# untitled.net
KiCad netlist of a schematic drawn in EAGLE
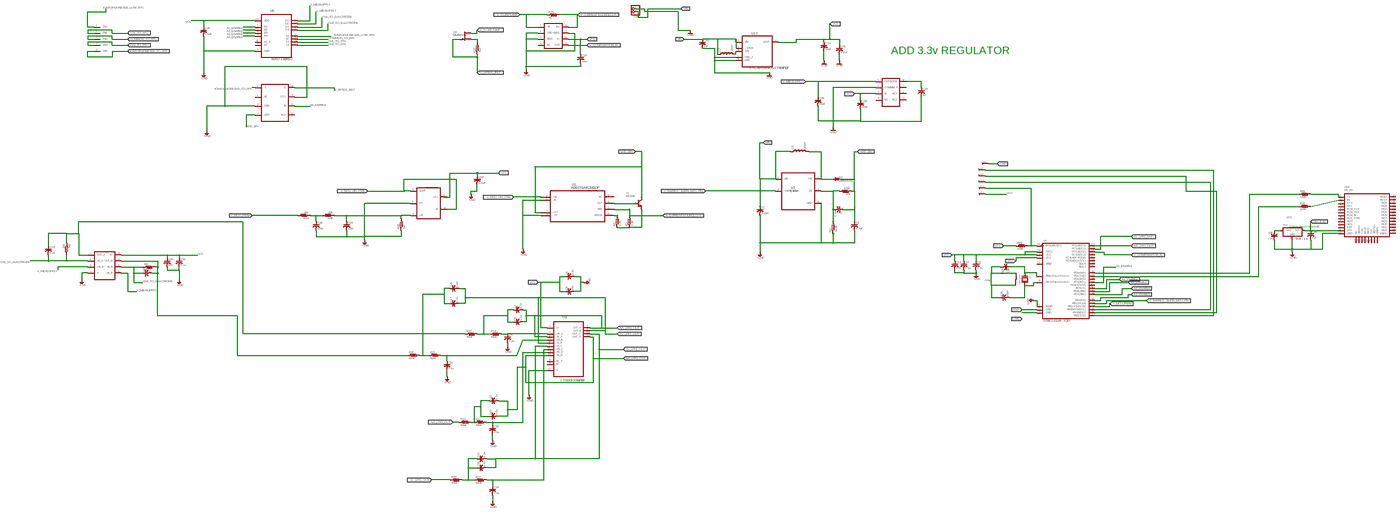
[diagram p0: schematic, sheet 1, overview]
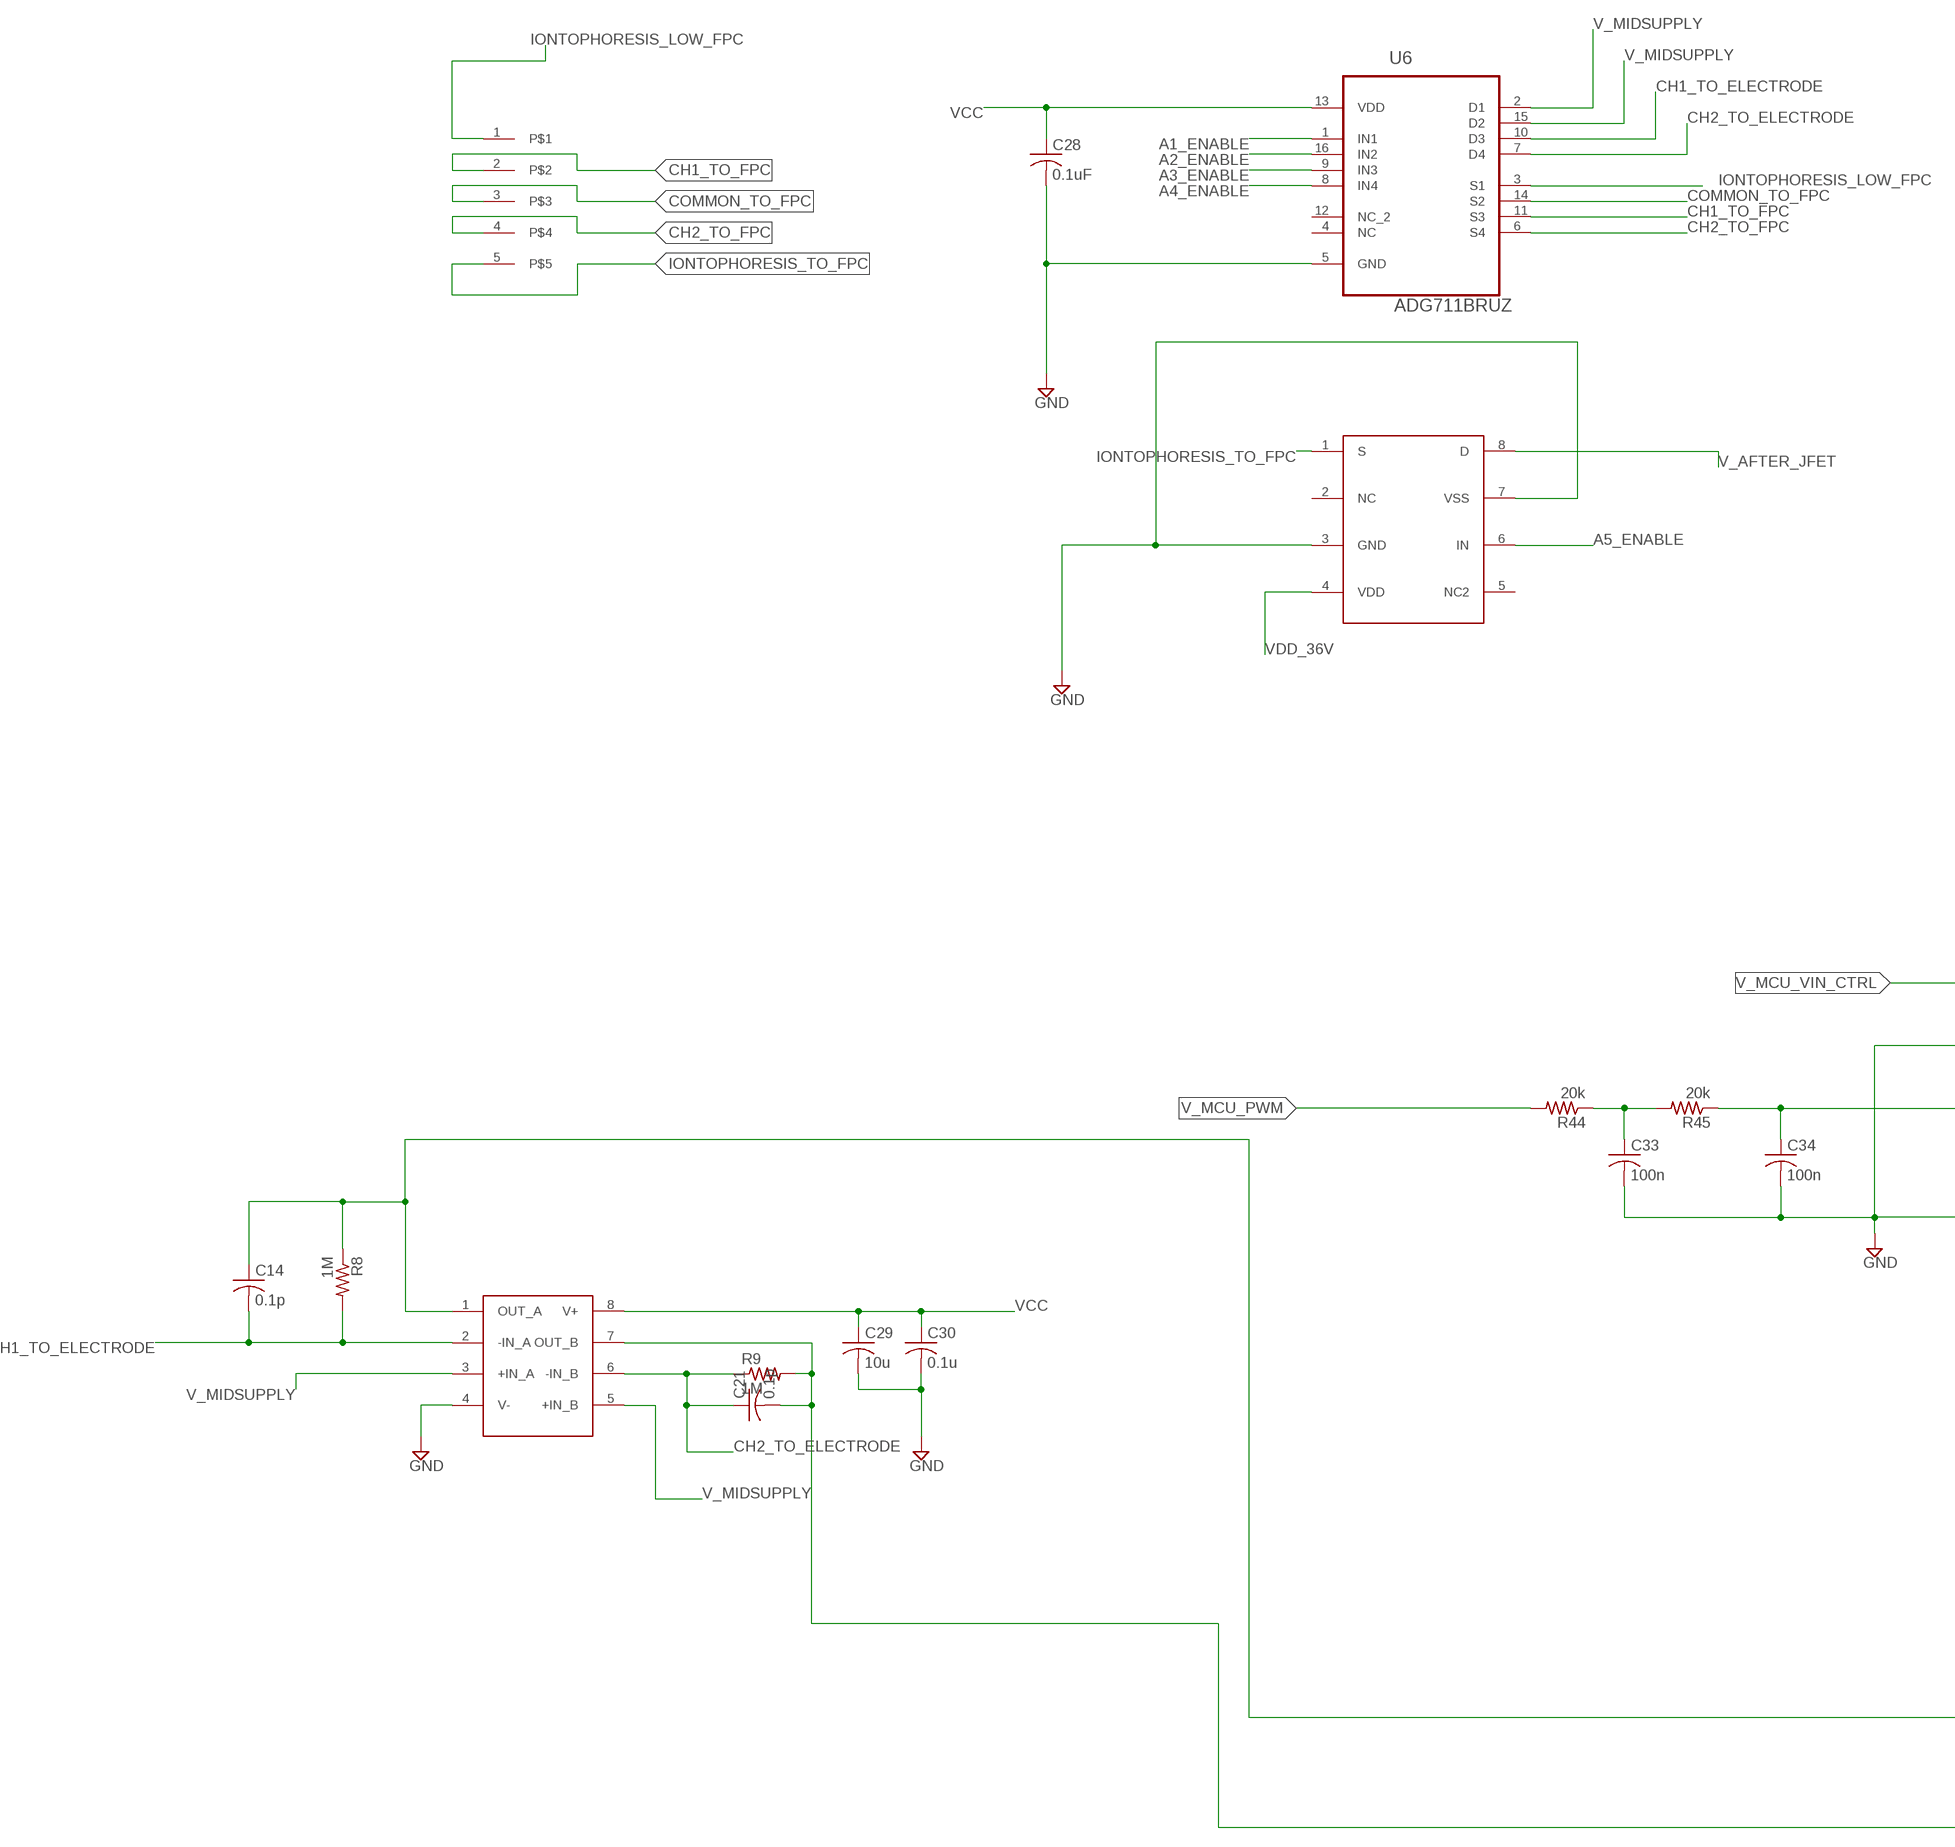
[diagram p1: schematic, sheet 1, part 1 of 4]
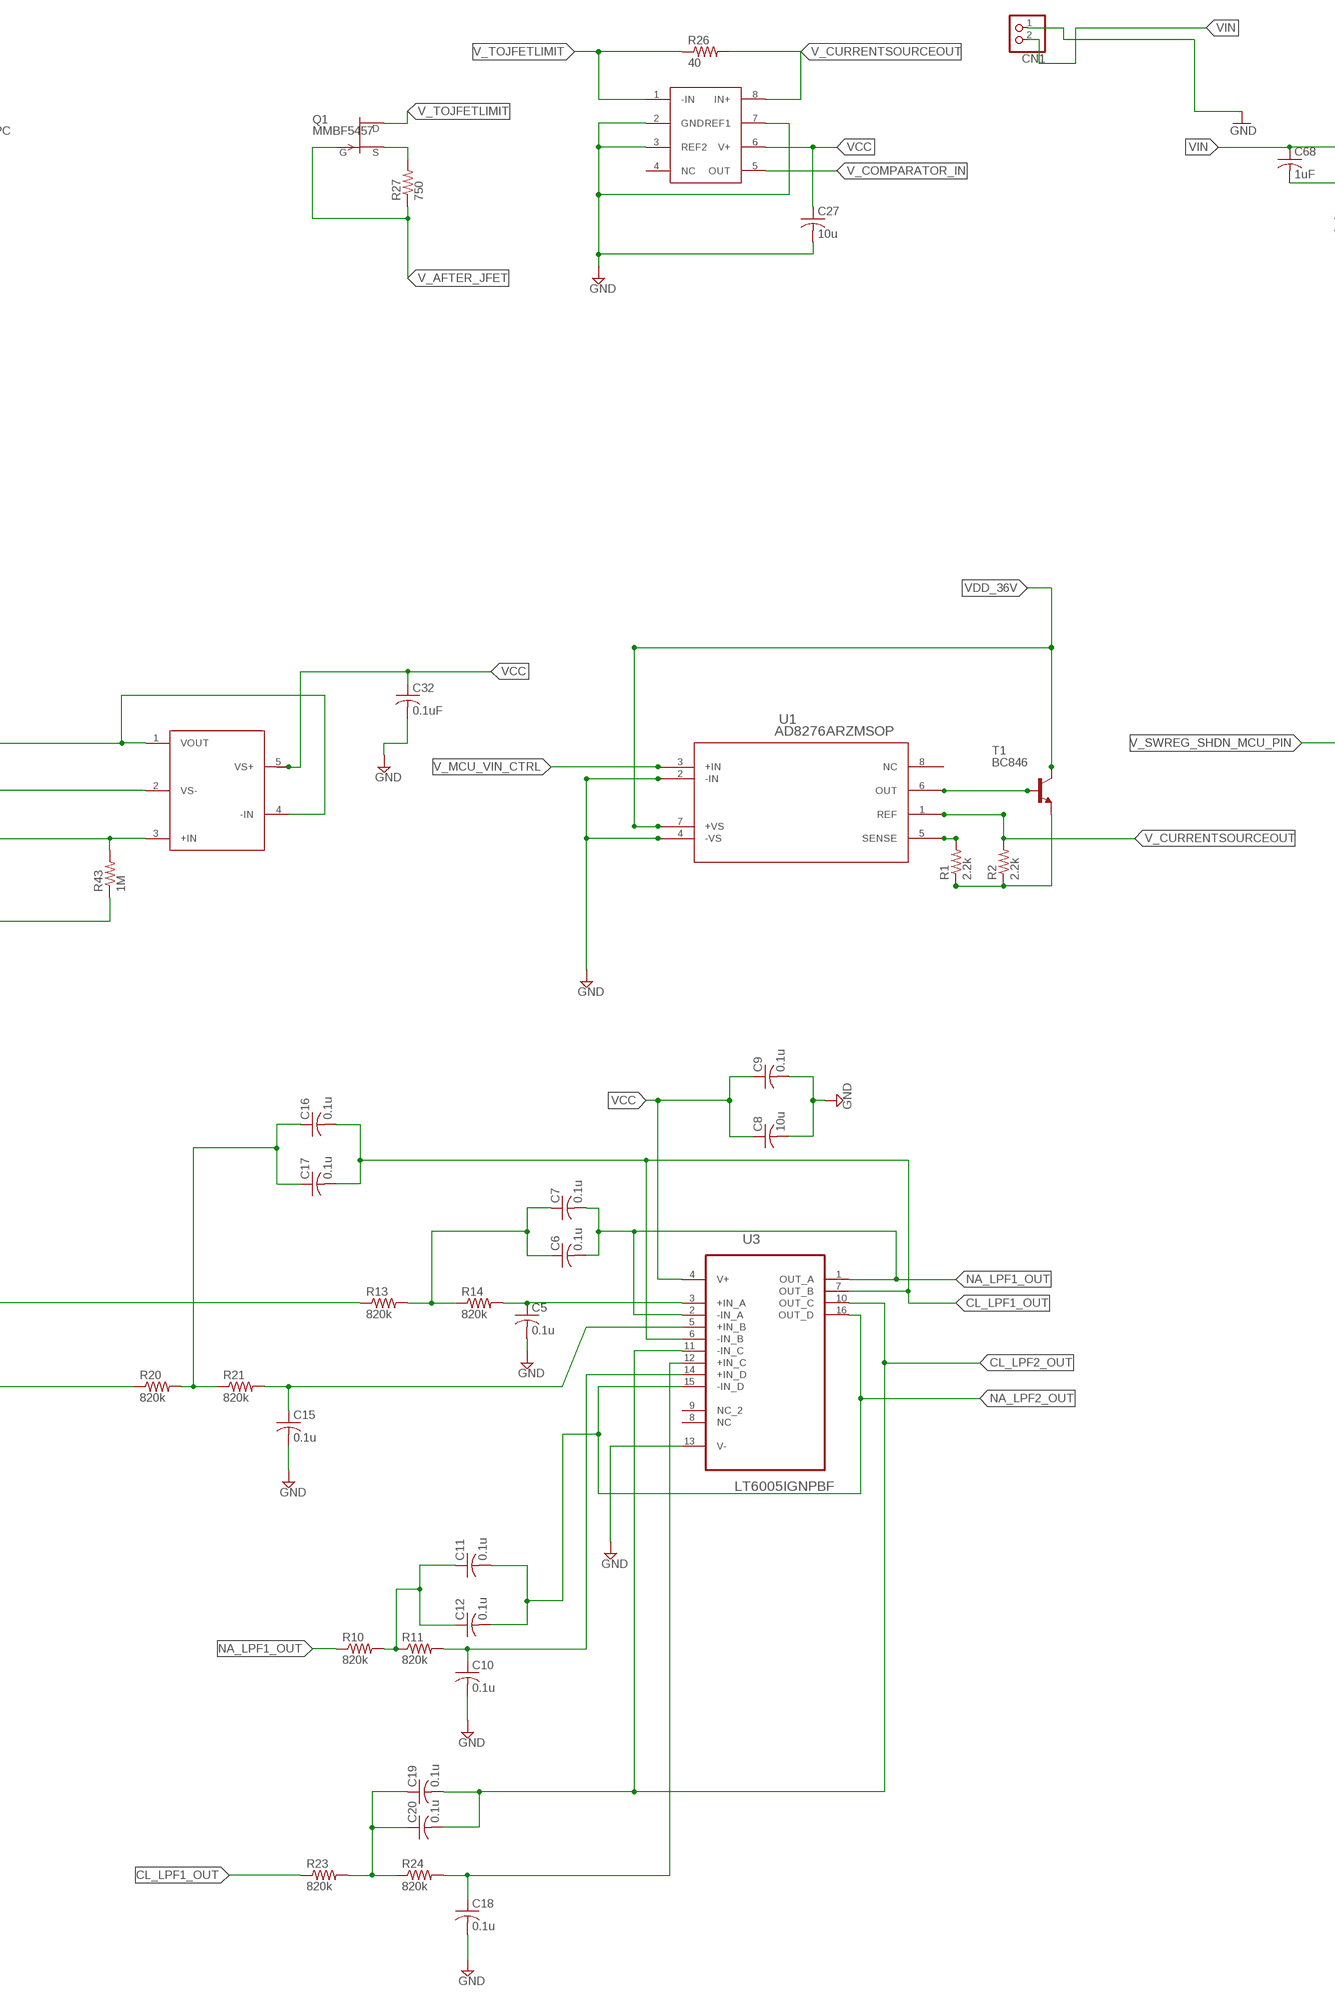
[diagram p2: schematic, sheet 1, part 2 of 4]
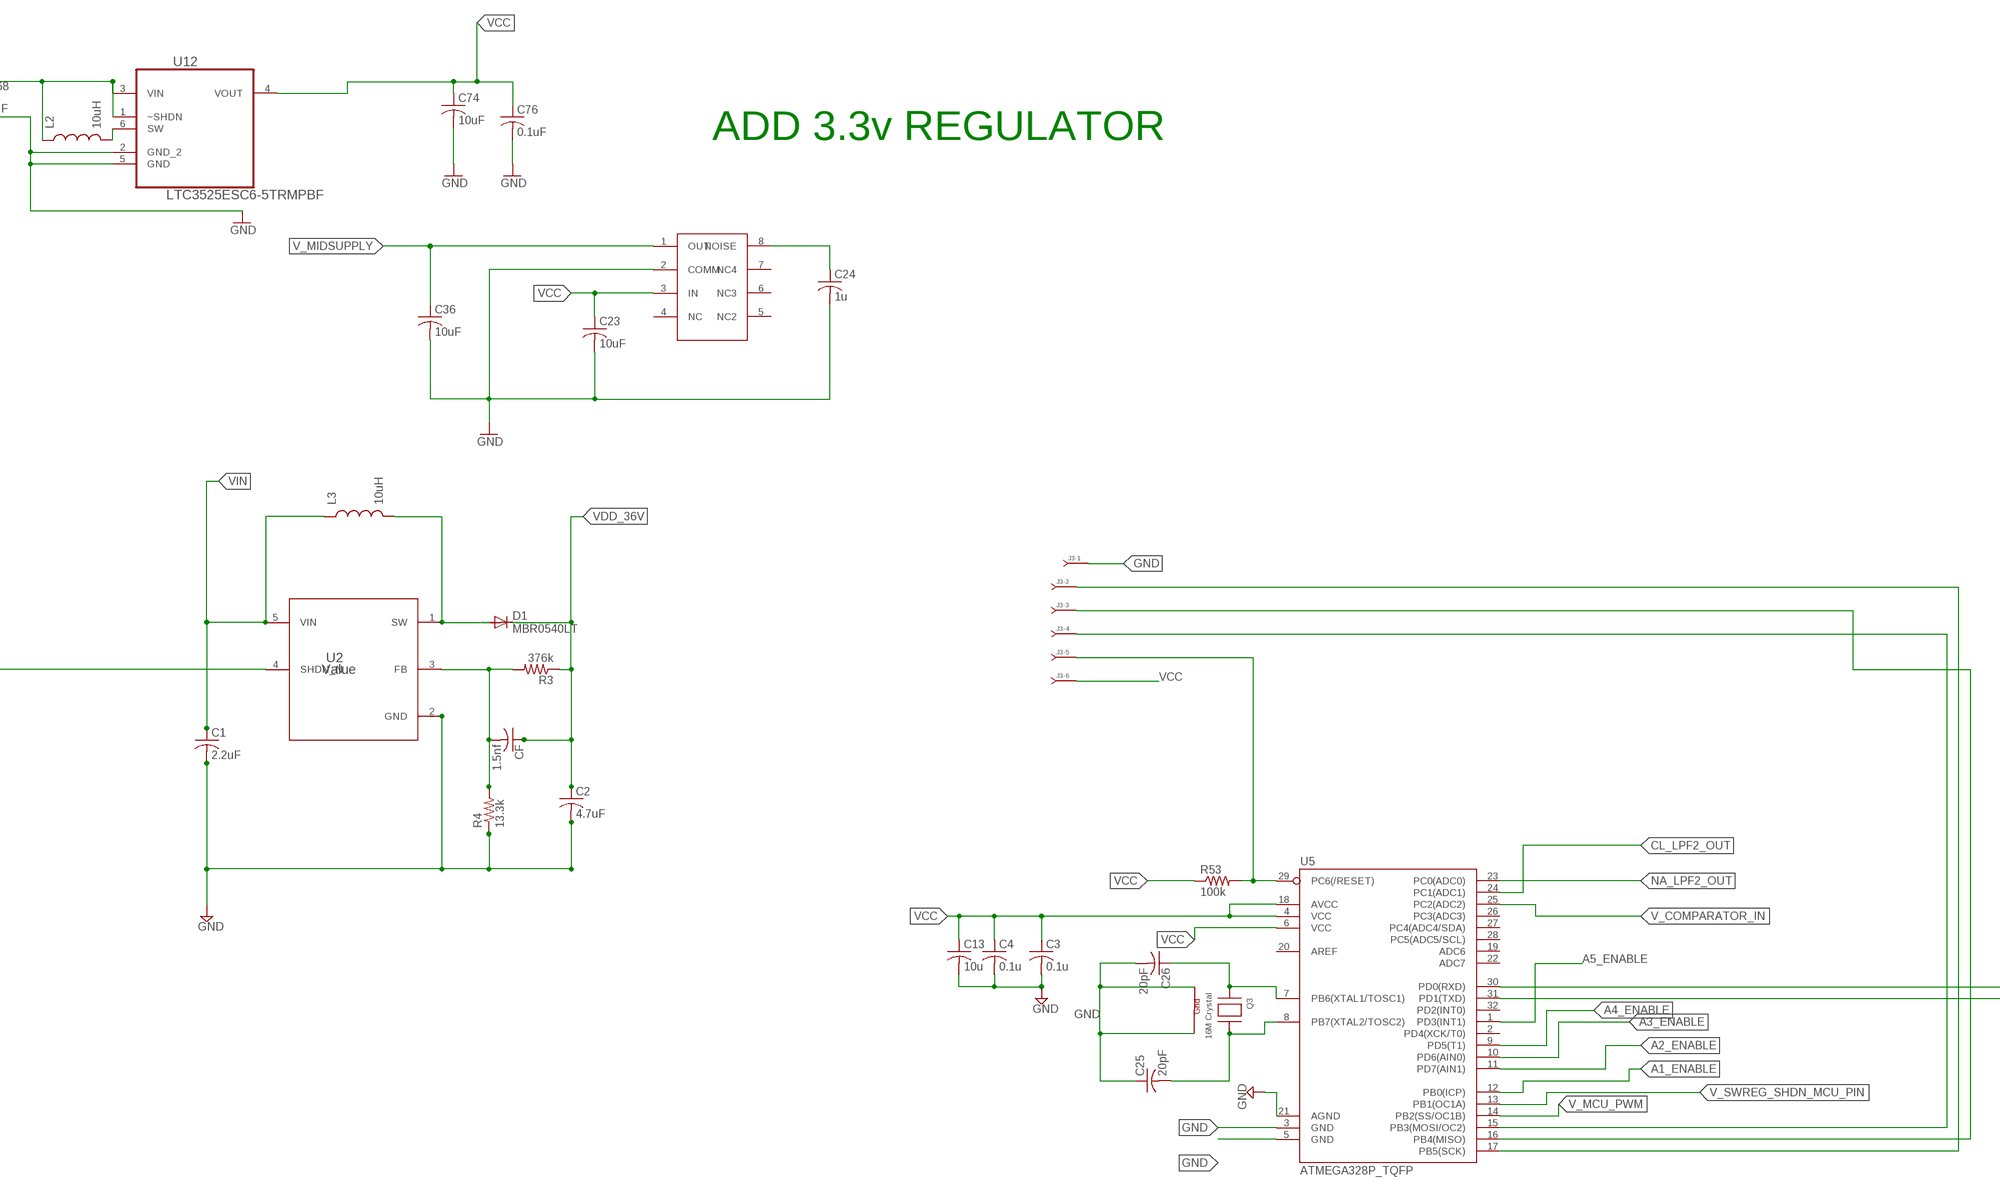
[diagram p3: schematic, sheet 1, part 3 of 4]
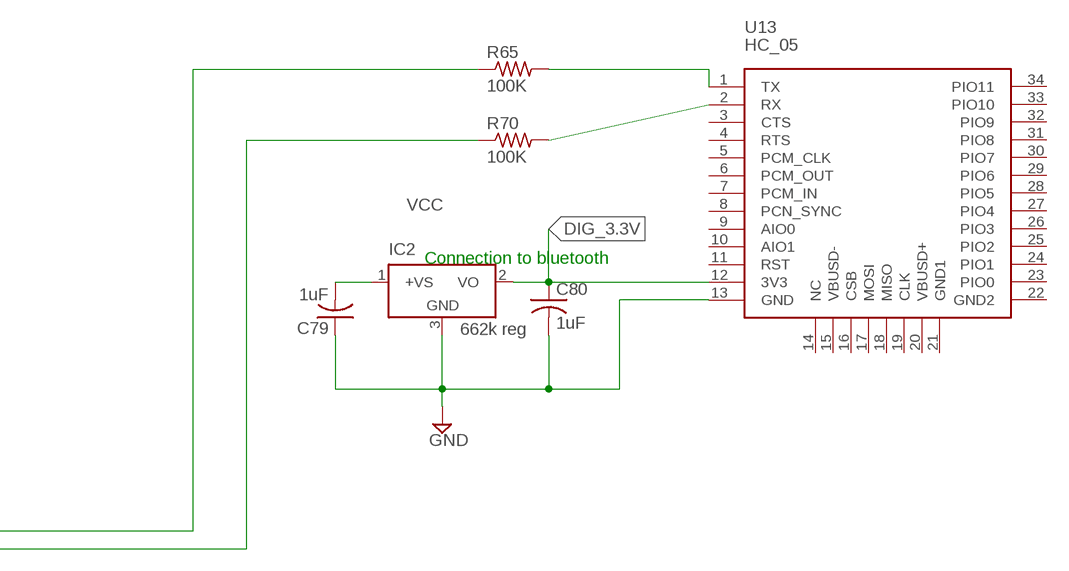
[diagram p4: schematic, sheet 1, part 4 of 4]

(export (version "E")
  (design (tool "Eeschema 10.0.6"))
  (components
    (comp (ref "C1")
      (value "2.2uF")
      (footprint "eagle-import:C0402")
      (libsource (lib "eagle-import") (part "resistor_C-USC0402"))
    )
    (comp (ref "C2")
      (value "4.7uF")
      (footprint "eagle-import:C0603")
      (libsource (lib "eagle-import") (part "resistor_C-USC0603"))
    )
    (comp (ref "C3")
      (value "0.1u")
      (footprint "eagle-import:C0201")
      (libsource (lib "eagle-import") (part "C-USC0201"))
    )
    (comp (ref "C4")
      (value "0.1u")
      (footprint "eagle-import:C0201")
      (libsource (lib "eagle-import") (part "C-USC0201"))
    )
    (comp (ref "C5")
      (value "0.1u")
      (footprint "eagle-import:C0201")
      (libsource (lib "eagle-import") (part "C-USC0201"))
    )
    (comp (ref "C6")
      (value "0.1u")
      (footprint "eagle-import:C0201")
      (libsource (lib "eagle-import") (part "C-USC0201"))
    )
    (comp (ref "C7")
      (value "0.1u")
      (footprint "eagle-import:C0201")
      (libsource (lib "eagle-import") (part "C-USC0201"))
    )
    (comp (ref "C8")
      (value "10u")
      (footprint "eagle-import:C0402")
      (libsource (lib "eagle-import") (part "resistor_C-USC0402"))
    )
    (comp (ref "C9")
      (value "0.1u")
      (footprint "eagle-import:C0201")
      (libsource (lib "eagle-import") (part "C-USC0201"))
    )
    (comp (ref "C10")
      (value "0.1u")
      (footprint "eagle-import:C0201")
      (libsource (lib "eagle-import") (part "C-USC0201"))
    )
    (comp (ref "C11")
      (value "0.1u")
      (footprint "eagle-import:C0201")
      (libsource (lib "eagle-import") (part "C-USC0201"))
    )
    (comp (ref "C12")
      (value "0.1u")
      (footprint "eagle-import:C0201")
      (libsource (lib "eagle-import") (part "C-USC0201"))
    )
    (comp (ref "C13")
      (value "10u")
      (footprint "eagle-import:C0402")
      (libsource (lib "eagle-import") (part "resistor_C-USC0402"))
    )
    (comp (ref "C14")
      (value "0.1p")
      (footprint "eagle-import:C0402")
      (libsource (lib "eagle-import") (part "resistor_C-USC0402"))
    )
    (comp (ref "C15")
      (value "0.1u")
      (footprint "eagle-import:C0201")
      (libsource (lib "eagle-import") (part "C-USC0201"))
    )
    (comp (ref "C16")
      (value "0.1u")
      (footprint "eagle-import:C0201")
      (libsource (lib "eagle-import") (part "C-USC0201"))
    )
    (comp (ref "C17")
      (value "0.1u")
      (footprint "eagle-import:C0201")
      (libsource (lib "eagle-import") (part "C-USC0201"))
    )
    (comp (ref "C18")
      (value "0.1u")
      (footprint "eagle-import:C0201")
      (libsource (lib "eagle-import") (part "C-USC0201"))
    )
    (comp (ref "C19")
      (value "0.1u")
      (footprint "eagle-import:C0201")
      (libsource (lib "eagle-import") (part "C-USC0201"))
    )
    (comp (ref "C20")
      (value "0.1u")
      (footprint "eagle-import:C0201")
      (libsource (lib "eagle-import") (part "C-USC0201"))
    )
    (comp (ref "C21")
      (value "0.1p")
      (footprint "eagle-import:C0402")
      (libsource (lib "eagle-import") (part "resistor_C-USC0402"))
    )
    (comp (ref "C23")
      (value "10uF")
      (footprint "eagle-import:C0402")
      (libsource (lib "eagle-import") (part "C-USC0402"))
    )
    (comp (ref "C24")
      (value "1u")
      (footprint "eagle-import:C0402")
      (libsource (lib "eagle-import") (part "C-USC0402"))
    )
    (comp (ref "C25")
      (value "20pF")
      (footprint "eagle-import:C0402")
      (libsource (lib "eagle-import") (part "C-USC0402"))
    )
    (comp (ref "C26")
      (value "20pF")
      (footprint "eagle-import:C0402")
      (libsource (lib "eagle-import") (part "C-USC0402"))
    )
    (comp (ref "C27")
      (value "10u")
      (footprint "eagle-import:C0402")
      (libsource (lib "eagle-import") (part "resistor_C-USC0402"))
    )
    (comp (ref "C28")
      (value "0.1uF")
      (footprint "eagle-import:C0201")
      (libsource (lib "eagle-import") (part "C-USC0201"))
    )
    (comp (ref "C29")
      (value "10u")
      (footprint "eagle-import:C0402")
      (libsource (lib "eagle-import") (part "resistor_C-USC0402"))
    )
    (comp (ref "C30")
      (value "0.1u")
      (footprint "eagle-import:C0201")
      (libsource (lib "eagle-import") (part "C-USC0201"))
    )
    (comp (ref "C32")
      (value "0.1uF")
      (footprint "eagle-import:C0201")
      (libsource (lib "eagle-import") (part "C-USC0201"))
    )
    (comp (ref "C33")
      (value "100n")
      (footprint "eagle-import:C0201")
      (libsource (lib "eagle-import") (part "C-USC0201"))
    )
    (comp (ref "C34")
      (value "100n")
      (footprint "eagle-import:C0201")
      (libsource (lib "eagle-import") (part "C-USC0201"))
    )
    (comp (ref "C36")
      (value "10uF")
      (footprint "eagle-import:C0402")
      (libsource (lib "eagle-import") (part "C-USC0402"))
    )
    (comp (ref "C68")
      (value "1uF")
      (footprint "eagle-import:C0402")
      (fields (field (name "MPN") "MC0402X105M6R3CT"))
      (libsource (lib "eagle-import") (part "C-USC0402"))
    )
    (comp (ref "C74")
      (value "10uF")
      (footprint "eagle-import:C0402")
      (libsource (lib "eagle-import") (part "C-USC0402"))
    )
    (comp (ref "C76")
      (value "0.1uF")
      (footprint "eagle-import:C0402")
      (libsource (lib "eagle-import") (part "C-USC0402"))
    )
    (comp (ref "C79")
      (value "1uF")
      (footprint "eagle-import:C0402")
      (fields (field (name "MPN") "MC0402X105M6R3CT"))
      (libsource (lib "eagle-import") (part "C-USC0402"))
    )
    (comp (ref "C80")
      (value "1uF")
      (footprint "eagle-import:C0402")
      (fields (field (name "MPN") "MC0402X105M6R3CT"))
      (libsource (lib "eagle-import") (part "C-USC0402"))
    )
    (comp (ref "CF")
      (value "1.5nf")
      (footprint "eagle-import:C0402")
      (libsource (lib "eagle-import") (part "resistor_C-USC0402"))
    )
    (comp (ref "CN1")
      (value "JST_2PIN-SMT")
      (footprint "eagle-import:JST-PH-2-SMT")
      (libsource (lib "eagle-import") (part "JST_2PIN-SMT"))
    )
    (comp (ref "D1")
      (value "MBR0540LT")
      (footprint "eagle-import:SOD123")
      (libsource (lib "eagle-import") (part "MBR0540LT"))
    )
    (comp (ref "IC2")
      (value "662k reg")
      (footprint "eagle-import:SOT23")
      (fields (field (name "MF") "NATIONAL SEMICONDUCTOR") (field (name "MPN") "LM5008MM/NOPB"))
      (libsource (lib "eagle-import") (part "LM50"))
    )
    (comp (ref "J3")
      (value "J-06-100-2X03")
      (footprint "eagle-import:HDR-100-2X03")
      (libsource (lib "eagle-import") (part "J-06-100-2X03"))
    )
    (comp (ref "L2")
      (value "10uH")
      (footprint "eagle-import:0805")
      (libsource (lib "eagle-import") (part "INDUCTOR0805"))
    )
    (comp (ref "L3")
      (value "10uH")
      (footprint "eagle-import:0805")
      (libsource (lib "eagle-import") (part "INDUCTOR0805"))
    )
    (comp (ref "Q1")
      (value "MMBF5457")
      (footprint "eagle-import:SOT23")
      (libsource (lib "eagle-import") (part "MMBF5457"))
    )
    (comp (ref "Q3")
      (value "16M Crystal")
      (footprint "eagle-import:NX3225")
      (libsource (lib "eagle-import") (part "XTAL-4-3225"))
    )
    (comp (ref "R1")
      (value "2.2k")
      (footprint "eagle-import:R0201")
      (libsource (lib "eagle-import") (part "R-US_R0201"))
    )
    (comp (ref "R2")
      (value "2.2k")
      (footprint "eagle-import:R0201")
      (libsource (lib "eagle-import") (part "R-US_R0201"))
    )
    (comp (ref "R3")
      (value "376k")
      (footprint "eagle-import:R0402")
      (libsource (lib "eagle-import") (part "R-US_R0402"))
    )
    (comp (ref "R4")
      (value "13.3k")
      (footprint "eagle-import:R0402")
      (libsource (lib "eagle-import") (part "R-US_R0402"))
    )
    (comp (ref "R8")
      (value "1M")
      (footprint "eagle-import:R0402")
      (libsource (lib "eagle-import") (part "R-US_R0402"))
    )
    (comp (ref "R9")
      (value "1M")
      (footprint "eagle-import:R0402")
      (libsource (lib "eagle-import") (part "R-US_R0402"))
    )
    (comp (ref "R10")
      (value "820k")
      (footprint "eagle-import:R0201")
      (libsource (lib "eagle-import") (part "R-US_R0201"))
    )
    (comp (ref "R11")
      (value "820k")
      (footprint "eagle-import:R0201")
      (libsource (lib "eagle-import") (part "R-US_R0201"))
    )
    (comp (ref "R13")
      (value "820k")
      (footprint "eagle-import:R0201")
      (libsource (lib "eagle-import") (part "R-US_R0201"))
    )
    (comp (ref "R14")
      (value "820k")
      (footprint "eagle-import:R0201")
      (libsource (lib "eagle-import") (part "R-US_R0201"))
    )
    (comp (ref "R20")
      (value "820k")
      (footprint "eagle-import:R0201")
      (libsource (lib "eagle-import") (part "R-US_R0201"))
    )
    (comp (ref "R21")
      (value "820k")
      (footprint "eagle-import:R0201")
      (libsource (lib "eagle-import") (part "R-US_R0201"))
    )
    (comp (ref "R23")
      (value "820k")
      (footprint "eagle-import:R0201")
      (libsource (lib "eagle-import") (part "R-US_R0201"))
    )
    (comp (ref "R24")
      (value "820k")
      (footprint "eagle-import:R0201")
      (libsource (lib "eagle-import") (part "R-US_R0201"))
    )
    (comp (ref "R26")
      (value "40")
      (footprint "eagle-import:R0201")
      (libsource (lib "eagle-import") (part "R-US_R0201"))
    )
    (comp (ref "R27")
      (value "750")
      (footprint "eagle-import:R0402")
      (libsource (lib "eagle-import") (part "R-US_R0402"))
    )
    (comp (ref "R43")
      (value "1M")
      (footprint "eagle-import:R0201")
      (libsource (lib "eagle-import") (part "R-US_R0201"))
    )
    (comp (ref "R44")
      (value "20k")
      (footprint "eagle-import:R0201")
      (libsource (lib "eagle-import") (part "R-US_R0201"))
    )
    (comp (ref "R45")
      (value "20k")
      (footprint "eagle-import:R0201")
      (libsource (lib "eagle-import") (part "R-US_R0201"))
    )
    (comp (ref "R53")
      (value "100k")
      (footprint "eagle-import:R0201")
      (libsource (lib "eagle-import") (part "R-US_R0201"))
    )
    (comp (ref "R65")
      (value "100K")
      (footprint "eagle-import:R0201")
      (libsource (lib "eagle-import") (part "R-US_R0201"))
    )
    (comp (ref "R70")
      (value "100K")
      (footprint "eagle-import:R0201")
      (libsource (lib "eagle-import") (part "R-US_R0201"))
    )
    (comp (ref "T1")
      (value "BC846")
      (footprint "eagle-import:SOT23")
      (libsource (lib "eagle-import") (part "BC846"))
    )
    (comp (ref "U$1")
      (value "ADG5401")
      (footprint "eagle-import:MSOP08")
      (libsource (lib "eagle-import") (part "ADG5401"))
    )
    (comp (ref "U$2")
      (value "AD8462")
      (footprint "eagle-import:MSOP08")
      (libsource (lib "eagle-import") (part "AD8462"))
    )
    (comp (ref "U$5")
      (value "LT1800")
      (footprint "eagle-import:SOT23-5")
      (libsource (lib "eagle-import") (part "LT1800"))
    )
    (comp (ref "U1")
      (value "AD8276ARZMSOP")
      (footprint "eagle-import:MSOP08")
      (libsource (lib "eagle-import") (part "AD8276ARZMSOP"))
    )
    (comp (ref "U2")
      (value "Value")
      (footprint "eagle-import:DBV0005A_N")
      (fields
        (field (name "MANUFACTURER") "Texas Instruments")
        (field (name "PARTNUMBER") "LMR64010XMFE/NOPB")
      )
      (libsource (lib "eagle-import") (part "LMR64010XMFE/NOPB"))
    )
    (comp (ref "U3")
      (value "LT6005IGNPBF")
      (footprint "eagle-import:SOP63P600X175-16N")
      (fields (field (name "MPN") "LT6005IGN#PBF"))
      (libsource (lib "eagle-import") (part "LT6005IGNPBF"))
    )
    (comp (ref "U4")
      (value "INA282")
      (footprint "eagle-import:SO08")
      (libsource (lib "eagle-import") (part "INA282"))
    )
    (comp (ref "U5")
      (value "ATMEGA328P_TQFP")
      (footprint "eagle-import:TQFP32-08")
      (libsource (lib "eagle-import") (part "ATMEGA328P_TQFP"))
    )
    (comp (ref "U6")
      (value "ADG711BRUZ")
      (footprint "eagle-import:SOP65P640X120-16N")
      (libsource (lib "eagle-import") (part "ADG711BRUZ"))
    )
    (comp (ref "U12")
      (value "LTC3525ESC6-5TRMPBF")
      (footprint "eagle-import:SOT65P210X100-6N")
      (fields (field (name "MPN") "LTC3525ESC6-5#TRMPBF") (field (name "OC_NEWARK") "unknown"))
      (libsource (lib "eagle-import") (part "LTC3525ESC6-5TRMPBF"))
    )
    (comp (ref "U13")
      (value "HC_05")
      (footprint "eagle-import:BLUETOOTH_SMD")
      (libsource (lib "eagle-import") (part "HC_05"))
    )
    (comp (ref "U15")
      (value "TLE2426IDR")
      (footprint "eagle-import:R_8")
      (libsource (lib "eagle-import") (part "TLE2426IDR"))
    )
    (comp (ref "U20")
      (value "FH12-5S-1SH")
      (footprint "eagle-import:FH12-5S-1SH")
      (libsource (lib "eagle-import") (part "FH12-5S-1SH"))
    )
  )
  (nets
    (net (code "1") (name "/A5_ENABLE") (class "Default")
      (node (ref "U$1") (pin "6") (pinfunction "IN_6") (pintype "bidirectional"))
      (node (ref "U5") (pin "1") (pinfunction "PD3(INT1)_1") (pintype "bidirectional"))
    )
    (net (code "2") (name "/CH1_TO_ELECTRODE") (class "Default")
      (node (ref "C14") (pin "2") (pinfunction "2_2") (pintype "passive"))
      (node (ref "R8") (pin "2") (pinfunction "2_2") (pintype "passive"))
      (node (ref "U$2") (pin "2") (pinfunction "-IN_A_2") (pintype "bidirectional"))
      (node (ref "U6") (pin "10") (pinfunction "D3_10") (pintype "bidirectional"))
    )
    (net (code "3") (name "/CH2_TO_ELECTRODE") (class "Default")
      (node (ref "C21") (pin "1") (pinfunction "1_1") (pintype "passive"))
      (node (ref "R9") (pin "1") (pinfunction "1_1") (pintype "passive"))
      (node (ref "U$2") (pin "6") (pinfunction "-IN_B_6") (pintype "bidirectional"))
      (node (ref "U6") (pin "7") (pinfunction "D4_7") (pintype "bidirectional"))
    )
    (net (code "4") (name "/IONTOPHORESIS_LOW_FPC") (class "Default")
      (node (ref "U20") (pin "1") (pinfunction "P$1_1") (pintype "bidirectional"))
      (node (ref "U6") (pin "3") (pinfunction "S1_3") (pintype "bidirectional"))
    )
    (net (code "5") (name "A1_ENABLE") (class "Default")
      (node (ref "U5") (pin "12") (pinfunction "PB0(ICP)_12") (pintype "bidirectional"))
      (node (ref "U6") (pin "1") (pinfunction "IN1_1") (pintype "input"))
    )
    (net (code "6") (name "A2_ENABLE") (class "Default")
      (node (ref "U5") (pin "11") (pinfunction "PD7(AIN1)_11") (pintype "bidirectional"))
      (node (ref "U6") (pin "16") (pinfunction "IN2_16") (pintype "input"))
    )
    (net (code "7") (name "A3_ENABLE") (class "Default")
      (node (ref "U5") (pin "10") (pinfunction "PD6(AIN0)_10") (pintype "bidirectional"))
      (node (ref "U6") (pin "9") (pinfunction "IN3_9") (pintype "input"))
    )
    (net (code "8") (name "A4_ENABLE") (class "Default")
      (node (ref "U5") (pin "9") (pinfunction "PD5(T1)_9") (pintype "bidirectional"))
      (node (ref "U6") (pin "8") (pinfunction "IN4_8") (pintype "input"))
    )
    (net (code "9") (name "CH1_TO_FPC") (class "Default")
      (node (ref "U20") (pin "2") (pinfunction "P$2_2") (pintype "bidirectional"))
      (node (ref "U6") (pin "11") (pinfunction "S3_11") (pintype "bidirectional"))
    )
    (net (code "10") (name "CH2_TO_FPC") (class "Default")
      (node (ref "U20") (pin "4") (pinfunction "P$4_4") (pintype "bidirectional"))
      (node (ref "U6") (pin "6") (pinfunction "S4_6") (pintype "bidirectional"))
    )
    (net (code "11") (name "CL_LPF1_OUT") (class "Default")
      (node (ref "C16") (pin "2") (pinfunction "2_2") (pintype "passive"))
      (node (ref "C17") (pin "2") (pinfunction "2_2") (pintype "passive"))
      (node (ref "R23") (pin "1") (pinfunction "1_1") (pintype "passive"))
      (node (ref "U3") (pin "6") (pinfunction "-IN_B_6") (pintype "input"))
      (node (ref "U3") (pin "7") (pinfunction "OUT_B_7") (pintype "output"))
    )
    (net (code "12") (name "CL_LPF2_OUT") (class "Default")
      (node (ref "C19") (pin "2") (pinfunction "2_2") (pintype "passive"))
      (node (ref "C20") (pin "2") (pinfunction "2_2") (pintype "passive"))
      (node (ref "U3") (pin "10") (pinfunction "OUT_C_10") (pintype "output"))
      (node (ref "U3") (pin "11") (pinfunction "-IN_C_11") (pintype "input"))
      (node (ref "U5") (pin "24") (pinfunction "PC1(ADC1)_24") (pintype "bidirectional"))
    )
    (net (code "13") (name "COMMON_TO_FPC") (class "Default")
      (node (ref "U20") (pin "3") (pinfunction "P$3_3") (pintype "bidirectional"))
      (node (ref "U6") (pin "14") (pinfunction "S2_14") (pintype "bidirectional"))
    )
    (net (code "14") (name "DIG_3.3V") (class "Default")
      (node (ref "C80") (pin "1") (pinfunction "1_1") (pintype "passive"))
      (node (ref "IC2") (pin "2") (pinfunction "VO_2") (pintype "input"))
      (node (ref "U13") (pin "12") (pinfunction "3V3_12") (pintype "bidirectional"))
    )
    (net (code "15") (name "GND") (class "Default")
      (node (ref "C1") (pin "2") (pinfunction "2_2") (pintype "passive"))
      (node (ref "C10") (pin "2") (pinfunction "2_2") (pintype "passive"))
      (node (ref "C13") (pin "2") (pinfunction "2_2") (pintype "passive"))
      (node (ref "C15") (pin "2") (pinfunction "2_2") (pintype "passive"))
      (node (ref "C18") (pin "2") (pinfunction "2_2") (pintype "passive"))
      (node (ref "C2") (pin "2") (pinfunction "2_2") (pintype "passive"))
      (node (ref "C23") (pin "2") (pinfunction "2_2") (pintype "passive"))
      (node (ref "C24") (pin "2") (pinfunction "2_2") (pintype "passive"))
      (node (ref "C25") (pin "1") (pinfunction "1_1") (pintype "passive"))
      (node (ref "C26") (pin "2") (pinfunction "2_2") (pintype "passive"))
      (node (ref "C27") (pin "2") (pinfunction "2_2") (pintype "passive"))
      (node (ref "C28") (pin "2") (pinfunction "2_2") (pintype "passive"))
      (node (ref "C29") (pin "2") (pinfunction "2_2") (pintype "passive"))
      (node (ref "C3") (pin "2") (pinfunction "2_2") (pintype "passive"))
      (node (ref "C30") (pin "2") (pinfunction "2_2") (pintype "passive"))
      (node (ref "C32") (pin "2") (pinfunction "2_2") (pintype "passive"))
      (node (ref "C33") (pin "2") (pinfunction "2_2") (pintype "passive"))
      (node (ref "C34") (pin "2") (pinfunction "2_2") (pintype "passive"))
      (node (ref "C36") (pin "2") (pinfunction "2_2") (pintype "passive"))
      (node (ref "C4") (pin "2") (pinfunction "2_2") (pintype "passive"))
      (node (ref "C5") (pin "2") (pinfunction "2_2") (pintype "passive"))
      (node (ref "C68") (pin "2") (pinfunction "2_2") (pintype "passive"))
      (node (ref "C74") (pin "2") (pinfunction "2_2") (pintype "passive"))
      (node (ref "C76") (pin "2") (pinfunction "2_2") (pintype "passive"))
      (node (ref "C79") (pin "1") (pinfunction "1_1") (pintype "passive"))
      (node (ref "C8") (pin "2") (pinfunction "2_2") (pintype "passive"))
      (node (ref "C80") (pin "2") (pinfunction "2_2") (pintype "passive"))
      (node (ref "C9") (pin "2") (pinfunction "2_2") (pintype "passive"))
      (node (ref "CN1") (pin "1") (pinfunction "2_1") (pintype "passive"))
      (node (ref "IC2") (pin "3") (pinfunction "GND_3") (pintype "power_in"))
      (node (ref "J3") (pin "1") (pinfunction "J_1") (pintype "passive"))
      (node (ref "Q3") (pin "2") (pinfunction "G2_2") (pintype "power_in"))
      (node (ref "Q3") (pin "4") (pinfunction "G1_4") (pintype "power_in"))
      (node (ref "R4") (pin "1") (pinfunction "1_1") (pintype "passive"))
      (node (ref "R43") (pin "1") (pinfunction "1_1") (pintype "passive"))
      (node (ref "U$1") (pin "3") (pinfunction "GND_3") (pintype "bidirectional"))
      (node (ref "U$1") (pin "7") (pinfunction "VSS_7") (pintype "bidirectional"))
      (node (ref "U$2") (pin "4") (pinfunction "V-_4") (pintype "bidirectional"))
      (node (ref "U$5") (pin "2") (pinfunction "VS-_2") (pintype "bidirectional"))
      (node (ref "U1") (pin "2") (pinfunction "-IN_2") (pintype "passive"))
      (node (ref "U1") (pin "4") (pinfunction "-VS_4") (pintype "passive"))
      (node (ref "U12") (pin "2") (pinfunction "GND_2_2") (pintype "passive"))
      (node (ref "U12") (pin "5") (pinfunction "GND_5") (pintype "passive"))
      (node (ref "U13") (pin "13") (pinfunction "GND_13") (pintype "bidirectional"))
      (node (ref "U15") (pin "2") (pinfunction "COMM_2") (pintype "bidirectional"))
      (node (ref "U2") (pin "2") (pinfunction "GND_2") (pintype "power_in"))
      (node (ref "U3") (pin "13") (pinfunction "V-_13") (pintype "power_in"))
      (node (ref "U4") (pin "2") (pinfunction "GND_2") (pintype "bidirectional"))
      (node (ref "U4") (pin "3") (pinfunction "REF2_3") (pintype "bidirectional"))
      (node (ref "U4") (pin "7") (pinfunction "REF1_7") (pintype "bidirectional"))
      (node (ref "U5") (pin "21") (pinfunction "AGND_21") (pintype "bidirectional"))
      (node (ref "U5") (pin "3") (pinfunction "GND_3") (pintype "bidirectional"))
      (node (ref "U5") (pin "5") (pinfunction "GND_5") (pintype "bidirectional"))
      (node (ref "U6") (pin "5") (pinfunction "GND_5") (pintype "passive"))
    )
    (net (code "16") (name "IONTOPHORESIS_TO_FPC") (class "Default")
      (node (ref "U$1") (pin "1") (pinfunction "S_1") (pintype "bidirectional"))
      (node (ref "U20") (pin "5") (pinfunction "P$5_5") (pintype "bidirectional"))
    )
    (net (code "17") (name "NA_LPF1_OUT") (class "Default")
      (node (ref "C6") (pin "2") (pinfunction "2_2") (pintype "passive"))
      (node (ref "C7") (pin "2") (pinfunction "2_2") (pintype "passive"))
      (node (ref "R10") (pin "1") (pinfunction "1_1") (pintype "passive"))
      (node (ref "U3") (pin "1") (pinfunction "OUT_A_1") (pintype "output"))
      (node (ref "U3") (pin "2") (pinfunction "-IN_A_2") (pintype "input"))
    )
    (net (code "18") (name "NA_LPF2_OUT") (class "Default")
      (node (ref "C11") (pin "2") (pinfunction "2_2") (pintype "passive"))
      (node (ref "C12") (pin "2") (pinfunction "2_2") (pintype "passive"))
      (node (ref "U3") (pin "15") (pinfunction "-IN_D_15") (pintype "input"))
      (node (ref "U3") (pin "16") (pinfunction "OUT_D_16") (pintype "output"))
      (node (ref "U5") (pin "23") (pinfunction "PC0(ADC0)_23") (pintype "bidirectional"))
    )
    (net (code "19") (name "Net-(C6-Pad1)") (class "Default")
      (node (ref "C6") (pin "1") (pinfunction "1_1") (pintype "passive"))
      (node (ref "C7") (pin "1") (pinfunction "1_1") (pintype "passive"))
      (node (ref "R13") (pin "2") (pinfunction "2_2") (pintype "passive"))
      (node (ref "R14") (pin "1") (pinfunction "1_1") (pintype "passive"))
    )
    (net (code "20") (name "Net-(C11-Pad1)") (class "Default")
      (node (ref "C11") (pin "1") (pinfunction "1_1") (pintype "passive"))
      (node (ref "C12") (pin "1") (pinfunction "1_1") (pintype "passive"))
      (node (ref "R10") (pin "2") (pinfunction "2_2") (pintype "passive"))
      (node (ref "R11") (pin "1") (pinfunction "1_1") (pintype "passive"))
    )
    (net (code "21") (name "Net-(C16-Pad1)") (class "Default")
      (node (ref "C16") (pin "1") (pinfunction "1_1") (pintype "passive"))
      (node (ref "C17") (pin "1") (pinfunction "1_1") (pintype "passive"))
      (node (ref "R20") (pin "2") (pinfunction "2_2") (pintype "passive"))
      (node (ref "R21") (pin "1") (pinfunction "1_1") (pintype "passive"))
    )
    (net (code "22") (name "Net-(C19-Pad1)") (class "Default")
      (node (ref "C19") (pin "1") (pinfunction "1_1") (pintype "passive"))
      (node (ref "C20") (pin "1") (pinfunction "1_1") (pintype "passive"))
      (node (ref "R23") (pin "2") (pinfunction "2_2") (pintype "passive"))
      (node (ref "R24") (pin "1") (pinfunction "1_1") (pintype "passive"))
    )
    (net (code "23") (name "Net-(C33-Pad1)") (class "Default")
      (node (ref "C33") (pin "1") (pinfunction "1_1") (pintype "passive"))
      (node (ref "R44") (pin "1") (pinfunction "1_1") (pintype "passive"))
      (node (ref "R45") (pin "2") (pinfunction "2_2") (pintype "passive"))
    )
    (net (code "24") (name "Net-(J3B-J)") (class "Default")
      (node (ref "J3") (pin "2") (pinfunction "J_2") (pintype "passive"))
      (node (ref "U5") (pin "17") (pinfunction "PB5(SCK)_17") (pintype "bidirectional"))
    )
    (net (code "25") (name "Net-(J3C-J)") (class "Default")
      (node (ref "J3") (pin "3") (pinfunction "J_3") (pintype "passive"))
      (node (ref "U5") (pin "16") (pinfunction "PB4(MISO)_16") (pintype "bidirectional"))
    )
    (net (code "26") (name "Net-(J3D-J)") (class "Default")
      (node (ref "J3") (pin "4") (pinfunction "J_4") (pintype "passive"))
      (node (ref "U5") (pin "15") (pinfunction "PB3(MOSI/OC2)_15") (pintype "bidirectional"))
    )
    (net (code "27") (name "Net-(J3E-J)") (class "Default")
      (node (ref "J3") (pin "5") (pinfunction "J_5") (pintype "passive"))
      (node (ref "R53") (pin "2") (pinfunction "2_2") (pintype "passive"))
      (node (ref "U5") (pin "29") (pinfunction "PC6(/RESET)_29") (pintype "bidirectional"))
    )
    (net (code "28") (name "Net-(Q1-S)") (class "Default")
      (node (ref "Q1") (pin "2") (pinfunction "S_2") (pintype "passive"))
      (node (ref "R27") (pin "2") (pinfunction "2_2") (pintype "passive"))
    )
    (net (code "29") (name "Net-(Q3-X1)") (class "Default")
      (node (ref "C26") (pin "1") (pinfunction "1_1") (pintype "passive"))
      (node (ref "Q3") (pin "1") (pinfunction "X1_1") (pintype "bidirectional"))
      (node (ref "U5") (pin "7") (pinfunction "PB6(XTAL1/TOSC1)_7") (pintype "bidirectional"))
    )
    (net (code "30") (name "Net-(Q3-X2)") (class "Default")
      (node (ref "C25") (pin "2") (pinfunction "2_2") (pintype "passive"))
      (node (ref "Q3") (pin "3") (pinfunction "X2_3") (pintype "bidirectional"))
      (node (ref "U5") (pin "8") (pinfunction "PB7(XTAL2/TOSC2)_8") (pintype "bidirectional"))
    )
    (net (code "31") (name "Net-(T1-B)") (class "Default")
      (node (ref "T1") (pin "1") (pinfunction "B_1") (pintype "passive"))
      (node (ref "U1") (pin "6") (pinfunction "OUT_6") (pintype "passive"))
    )
    (net (code "32") (name "Net-(T1-E)") (class "Default")
      (node (ref "R1") (pin "1") (pinfunction "1_1") (pintype "passive"))
      (node (ref "R2") (pin "1") (pinfunction "1_1") (pintype "passive"))
      (node (ref "T1") (pin "2") (pinfunction "E_2") (pintype "passive"))
    )
    (net (code "33") (name "Net-(U$2-OUT_A)") (class "Default")
      (node (ref "C14") (pin "1") (pinfunction "1_1") (pintype "passive"))
      (node (ref "R13") (pin "1") (pinfunction "1_1") (pintype "passive"))
      (node (ref "R8") (pin "1") (pinfunction "1_1") (pintype "passive"))
      (node (ref "U$2") (pin "1") (pinfunction "OUT_A_1") (pintype "bidirectional"))
    )
    (net (code "34") (name "Net-(U$2-OUT_B)") (class "Default")
      (node (ref "C21") (pin "2") (pinfunction "2_2") (pintype "passive"))
      (node (ref "R20") (pin "1") (pinfunction "1_1") (pintype "passive"))
      (node (ref "R9") (pin "2") (pinfunction "2_2") (pintype "passive"))
      (node (ref "U$2") (pin "7") (pinfunction "OUT_B_7") (pintype "bidirectional"))
    )
    (net (code "35") (name "Net-(U$5-+IN)") (class "Default")
      (node (ref "C34") (pin "1") (pinfunction "1_1") (pintype "passive"))
      (node (ref "R43") (pin "2") (pinfunction "2_2") (pintype "passive"))
      (node (ref "R45") (pin "1") (pinfunction "1_1") (pintype "passive"))
      (node (ref "U$5") (pin "3") (pinfunction "+IN_3") (pintype "bidirectional"))
    )
    (net (code "36") (name "Net-(U1-SENSE)") (class "Default")
      (node (ref "R1") (pin "2") (pinfunction "2_2") (pintype "passive"))
      (node (ref "U1") (pin "5") (pinfunction "SENSE_5") (pintype "passive"))
    )
    (net (code "37") (name "Net-(U2-FB)") (class "Default")
      (node (ref "CF") (pin "2") (pinfunction "2_2") (pintype "passive"))
      (node (ref "R3") (pin "2") (pinfunction "2_2") (pintype "passive"))
      (node (ref "R4") (pin "2") (pinfunction "2_2") (pintype "passive"))
      (node (ref "U2") (pin "3") (pinfunction "FB_3") (pintype "input"))
    )
    (net (code "38") (name "Net-(U2-SW)") (class "Default")
      (node (ref "D1") (pin "A") (pinfunction "A_A") (pintype "passive"))
      (node (ref "L3") (pin "2") (pinfunction "2_2") (pintype "passive"))
      (node (ref "U2") (pin "1") (pinfunction "SW_1") (pintype "power_in"))
    )
    (net (code "39") (name "Net-(U3-+IN_A)") (class "Default")
      (node (ref "C5") (pin "1") (pinfunction "1_1") (pintype "passive"))
      (node (ref "R14") (pin "2") (pinfunction "2_2") (pintype "passive"))
      (node (ref "U3") (pin "3") (pinfunction "+IN_A_3") (pintype "input"))
    )
    (net (code "40") (name "Net-(U3-+IN_B)") (class "Default")
      (node (ref "C15") (pin "1") (pinfunction "1_1") (pintype "passive"))
      (node (ref "R21") (pin "2") (pinfunction "2_2") (pintype "passive"))
      (node (ref "U3") (pin "5") (pinfunction "+IN_B_5") (pintype "input"))
    )
    (net (code "41") (name "Net-(U3-+IN_C)") (class "Default")
      (node (ref "C18") (pin "1") (pinfunction "1_1") (pintype "passive"))
      (node (ref "R24") (pin "2") (pinfunction "2_2") (pintype "passive"))
      (node (ref "U3") (pin "12") (pinfunction "+IN_C_12") (pintype "input"))
    )
    (net (code "42") (name "Net-(U3-+IN_D)") (class "Default")
      (node (ref "C10") (pin "1") (pinfunction "1_1") (pintype "passive"))
      (node (ref "R11") (pin "2") (pinfunction "2_2") (pintype "passive"))
      (node (ref "U3") (pin "14") (pinfunction "+IN_D_14") (pintype "input"))
    )
    (net (code "43") (name "Net-(U5-PD0(RXD))") (class "Default")
      (node (ref "R65") (pin "1") (pinfunction "1_1") (pintype "passive"))
      (node (ref "U5") (pin "30") (pinfunction "PD0(RXD)_30") (pintype "bidirectional"))
    )
    (net (code "44") (name "Net-(U5-PD1(TXD))") (class "Default")
      (node (ref "R70") (pin "1") (pinfunction "1_1") (pintype "passive"))
      (node (ref "U5") (pin "31") (pinfunction "PD1(TXD)_31") (pintype "bidirectional"))
    )
    (net (code "45") (name "Net-(U12-SW)") (class "Default")
      (node (ref "L2") (pin "2") (pinfunction "2_2") (pintype "passive"))
      (node (ref "U12") (pin "6") (pinfunction "SW_6") (pintype "input"))
    )
    (net (code "46") (name "Net-(U13-RX)") (class "Default")
      (node (ref "R70") (pin "2") (pinfunction "2_2") (pintype "passive"))
      (node (ref "U13") (pin "2") (pinfunction "RX_2") (pintype "bidirectional"))
    )
    (net (code "47") (name "Net-(U13-TX)") (class "Default")
      (node (ref "R65") (pin "2") (pinfunction "2_2") (pintype "passive"))
      (node (ref "U13") (pin "1") (pinfunction "TX_1") (pintype "bidirectional"))
    )
    (net (code "48") (name "Net-(U15-NOISE)") (class "Default")
      (node (ref "C24") (pin "1") (pinfunction "1_1") (pintype "passive"))
      (node (ref "U15") (pin "8") (pinfunction "NOISE_8") (pintype "bidirectional"))
    )
    (net (code "49") (name "VCC") (class "Default")
      (node (ref "C13") (pin "1") (pinfunction "1_1") (pintype "passive"))
      (node (ref "C23") (pin "1") (pinfunction "1_1") (pintype "passive"))
      (node (ref "C27") (pin "1") (pinfunction "1_1") (pintype "passive"))
      (node (ref "C28") (pin "1") (pinfunction "1_1") (pintype "passive"))
      (node (ref "C29") (pin "1") (pinfunction "1_1") (pintype "passive"))
      (node (ref "C3") (pin "1") (pinfunction "1_1") (pintype "passive"))
      (node (ref "C30") (pin "1") (pinfunction "1_1") (pintype "passive"))
      (node (ref "C32") (pin "1") (pinfunction "1_1") (pintype "passive"))
      (node (ref "C4") (pin "1") (pinfunction "1_1") (pintype "passive"))
      (node (ref "C74") (pin "1") (pinfunction "1_1") (pintype "passive"))
      (node (ref "C76") (pin "1") (pinfunction "1_1") (pintype "passive"))
      (node (ref "C79") (pin "2") (pinfunction "2_2") (pintype "passive"))
      (node (ref "C8") (pin "1") (pinfunction "1_1") (pintype "passive"))
      (node (ref "C9") (pin "1") (pinfunction "1_1") (pintype "passive"))
      (node (ref "IC2") (pin "1") (pinfunction "+VS_1") (pintype "input"))
      (node (ref "J3") (pin "6") (pinfunction "J_6") (pintype "passive"))
      (node (ref "R53") (pin "1") (pinfunction "1_1") (pintype "passive"))
      (node (ref "U$2") (pin "8") (pinfunction "V+_8") (pintype "bidirectional"))
      (node (ref "U$5") (pin "5") (pinfunction "VS+_5") (pintype "bidirectional"))
      (node (ref "U12") (pin "4") (pinfunction "VOUT_4") (pintype "output"))
      (node (ref "U15") (pin "3") (pinfunction "IN_3") (pintype "bidirectional"))
      (node (ref "U3") (pin "4") (pinfunction "V+_4") (pintype "power_in"))
      (node (ref "U4") (pin "6") (pinfunction "V+_6") (pintype "bidirectional"))
      (node (ref "U5") (pin "18") (pinfunction "AVCC_18") (pintype "bidirectional"))
      (node (ref "U5") (pin "4") (pinfunction "VCC_4") (pintype "bidirectional"))
      (node (ref "U5") (pin "6") (pinfunction "VCC_6") (pintype "bidirectional"))
      (node (ref "U6") (pin "13") (pinfunction "VDD_13") (pintype "power_in"))
    )
    (net (code "50") (name "VDD_36V") (class "Default")
      (node (ref "C2") (pin "1") (pinfunction "1_1") (pintype "passive"))
      (node (ref "CF") (pin "1") (pinfunction "1_1") (pintype "passive"))
      (node (ref "D1") (pin "C") (pinfunction "C_C") (pintype "passive"))
      (node (ref "R3") (pin "1") (pinfunction "1_1") (pintype "passive"))
      (node (ref "T1") (pin "3") (pinfunction "C_3") (pintype "passive"))
      (node (ref "U$1") (pin "4") (pinfunction "VDD_4") (pintype "bidirectional"))
      (node (ref "U1") (pin "7") (pinfunction "+VS_7") (pintype "passive"))
    )
    (net (code "51") (name "VIN") (class "Default")
      (node (ref "C1") (pin "1") (pinfunction "1_1") (pintype "passive"))
      (node (ref "C68") (pin "1") (pinfunction "1_1") (pintype "passive"))
      (node (ref "CN1") (pin "2") (pinfunction "1_2") (pintype "passive"))
      (node (ref "L2") (pin "1") (pinfunction "1_1") (pintype "passive"))
      (node (ref "L3") (pin "1") (pinfunction "1_1") (pintype "passive"))
      (node (ref "U12") (pin "1") (pinfunction "~{SHDN}_1") (pintype "input"))
      (node (ref "U12") (pin "3") (pinfunction "VIN_3") (pintype "input"))
      (node (ref "U2") (pin "5") (pinfunction "VIN_5") (pintype "power_in"))
    )
    (net (code "52") (name "V_AFTER_JFET") (class "Default")
      (node (ref "Q1") (pin "3") (pinfunction "G_3") (pintype "passive"))
      (node (ref "R27") (pin "1") (pinfunction "1_1") (pintype "passive"))
      (node (ref "U$1") (pin "8") (pinfunction "D_8") (pintype "bidirectional"))
    )
    (net (code "53") (name "V_COMPARATOR_IN") (class "Default")
      (node (ref "U4") (pin "5") (pinfunction "OUT_5") (pintype "bidirectional"))
      (node (ref "U5") (pin "25") (pinfunction "PC2(ADC2)_25") (pintype "bidirectional"))
    )
    (net (code "54") (name "V_CURRENTSOURCEOUT") (class "Default")
      (node (ref "R2") (pin "2") (pinfunction "2_2") (pintype "passive"))
      (node (ref "R26") (pin "2") (pinfunction "2_2") (pintype "passive"))
      (node (ref "U1") (pin "1") (pinfunction "REF_1") (pintype "passive"))
      (node (ref "U4") (pin "8") (pinfunction "IN+_8") (pintype "bidirectional"))
    )
    (net (code "55") (name "V_MCU_PWM") (class "Default")
      (node (ref "R44") (pin "2") (pinfunction "2_2") (pintype "passive"))
      (node (ref "U5") (pin "14") (pinfunction "PB2(SS/OC1B)_14") (pintype "bidirectional"))
    )
    (net (code "56") (name "V_MCU_VIN_CTRL") (class "Default")
      (node (ref "U$5") (pin "1") (pinfunction "VOUT_1") (pintype "bidirectional"))
      (node (ref "U$5") (pin "4") (pinfunction "-IN_4") (pintype "bidirectional"))
      (node (ref "U1") (pin "3") (pinfunction "+IN_3") (pintype "passive"))
    )
    (net (code "57") (name "V_MIDSUPPLY") (class "Default")
      (node (ref "C36") (pin "1") (pinfunction "1_1") (pintype "passive"))
      (node (ref "U$2") (pin "3") (pinfunction "+IN_A_3") (pintype "bidirectional"))
      (node (ref "U$2") (pin "5") (pinfunction "+IN_B_5") (pintype "bidirectional"))
      (node (ref "U15") (pin "1") (pinfunction "OUT_1") (pintype "bidirectional"))
      (node (ref "U6") (pin "15") (pinfunction "D2_15") (pintype "bidirectional"))
      (node (ref "U6") (pin "2") (pinfunction "D1_2") (pintype "bidirectional"))
    )
    (net (code "58") (name "V_SWREG_SHDN_MCU_PIN") (class "Default")
      (node (ref "U2") (pin "4") (pinfunction "SHDN_N_4") (pintype "input"))
      (node (ref "U5") (pin "13") (pinfunction "PB1(OC1A)_13") (pintype "bidirectional"))
    )
    (net (code "59") (name "V_TOJFETLIMIT") (class "Default")
      (node (ref "Q1") (pin "1") (pinfunction "D_1") (pintype "passive"))
      (node (ref "R26") (pin "1") (pinfunction "1_1") (pintype "passive"))
      (node (ref "U4") (pin "1") (pinfunction "-IN_1") (pintype "bidirectional"))
    )
    (net (code "60") (name "unconnected-(U$1-NC-Pad2)") (class "Default")
      (node (ref "U$1") (pin "2") (pinfunction "NC_2") (pintype "bidirectional"))
    )
    (net (code "61") (name "unconnected-(U$1-NC2-Pad5)") (class "Default")
      (node (ref "U$1") (pin "5") (pinfunction "NC2_5") (pintype "bidirectional"))
    )
    (net (code "62") (name "unconnected-(U1-NC-Pad8)") (class "Default")
      (node (ref "U1") (pin "8") (pinfunction "NC_8") (pintype "passive"))
    )
    (net (code "63") (name "unconnected-(U3-NC-Pad8)") (class "Default")
      (node (ref "U3") (pin "8") (pinfunction "NC_8") (pintype "no_connect"))
    )
    (net (code "64") (name "unconnected-(U3-NC_2-Pad9)") (class "Default")
      (node (ref "U3") (pin "9") (pinfunction "NC_2_9") (pintype "no_connect"))
    )
    (net (code "65") (name "unconnected-(U4-NC-Pad4)") (class "Default")
      (node (ref "U4") (pin "4") (pinfunction "NC_4") (pintype "bidirectional"))
    )
    (net (code "66") (name "unconnected-(U5-ADC6-Pad19)") (class "Default")
      (node (ref "U5") (pin "19") (pinfunction "ADC6_19") (pintype "bidirectional"))
    )
    (net (code "67") (name "unconnected-(U5-ADC7-Pad22)") (class "Default")
      (node (ref "U5") (pin "22") (pinfunction "ADC7_22") (pintype "bidirectional"))
    )
    (net (code "68") (name "unconnected-(U5-AREF-Pad20)") (class "Default")
      (node (ref "U5") (pin "20") (pinfunction "AREF_20") (pintype "bidirectional"))
    )
    (net (code "69") (name "unconnected-(U5-PC3(ADC3)-Pad26)") (class "Default")
      (node (ref "U5") (pin "26") (pinfunction "PC3(ADC3)_26") (pintype "bidirectional"))
    )
    (net (code "70") (name "unconnected-(U5-PC4(ADC4{slash}SDA)-Pad27)") (class "Default")
      (node (ref "U5") (pin "27") (pinfunction "PC4(ADC4/SDA)_27") (pintype "bidirectional"))
    )
    (net (code "71") (name "unconnected-(U5-PC5(ADC5{slash}SCL)-Pad28)") (class "Default")
      (node (ref "U5") (pin "28") (pinfunction "PC5(ADC5/SCL)_28") (pintype "bidirectional"))
    )
    (net (code "72") (name "unconnected-(U5-PD2(INT0)-Pad32)") (class "Default")
      (node (ref "U5") (pin "32") (pinfunction "PD2(INT0)_32") (pintype "bidirectional"))
    )
    (net (code "73") (name "unconnected-(U5-PD4(XCK{slash}T0)-Pad2)") (class "Default")
      (node (ref "U5") (pin "2") (pinfunction "PD4(XCK/T0)_2") (pintype "bidirectional"))
    )
    (net (code "74") (name "unconnected-(U6-NC-Pad4)") (class "Default")
      (node (ref "U6") (pin "4") (pinfunction "NC_4") (pintype "no_connect"))
    )
    (net (code "75") (name "unconnected-(U6-NC_2-Pad12)") (class "Default")
      (node (ref "U6") (pin "12") (pinfunction "NC_2_12") (pintype "no_connect"))
    )
    (net (code "76") (name "unconnected-(U13-AIO0-Pad9)") (class "Default")
      (node (ref "U13") (pin "9") (pinfunction "AIO0_9") (pintype "bidirectional"))
    )
    (net (code "77") (name "unconnected-(U13-AIO1-Pad10)") (class "Default")
      (node (ref "U13") (pin "10") (pinfunction "AIO1_10") (pintype "bidirectional"))
    )
    (net (code "78") (name "unconnected-(U13-CLK-Pad19)") (class "Default")
      (node (ref "U13") (pin "19") (pinfunction "CLK_19") (pintype "bidirectional"))
    )
    (net (code "79") (name "unconnected-(U13-CSB-Pad16)") (class "Default")
      (node (ref "U13") (pin "16") (pinfunction "CSB_16") (pintype "bidirectional"))
    )
    (net (code "80") (name "unconnected-(U13-CTS-Pad3)") (class "Default")
      (node (ref "U13") (pin "3") (pinfunction "CTS_3") (pintype "bidirectional"))
    )
    (net (code "81") (name "unconnected-(U13-GND1-Pad21)") (class "Default")
      (node (ref "U13") (pin "21") (pinfunction "GND1_21") (pintype "bidirectional"))
    )
    (net (code "82") (name "unconnected-(U13-GND2-Pad22)") (class "Default")
      (node (ref "U13") (pin "22") (pinfunction "GND2_22") (pintype "bidirectional"))
    )
    (net (code "83") (name "unconnected-(U13-MISO-Pad18)") (class "Default")
      (node (ref "U13") (pin "18") (pinfunction "MISO_18") (pintype "bidirectional"))
    )
    (net (code "84") (name "unconnected-(U13-MOSI-Pad17)") (class "Default")
      (node (ref "U13") (pin "17") (pinfunction "MOSI_17") (pintype "bidirectional"))
    )
    (net (code "85") (name "unconnected-(U13-NC-Pad14)") (class "Default")
      (node (ref "U13") (pin "14") (pinfunction "NC_14") (pintype "bidirectional"))
    )
    (net (code "86") (name "unconnected-(U13-PCM_CLK-Pad5)") (class "Default")
      (node (ref "U13") (pin "5") (pinfunction "PCM_CLK_5") (pintype "bidirectional"))
    )
    (net (code "87") (name "unconnected-(U13-PCM_IN-Pad7)") (class "Default")
      (node (ref "U13") (pin "7") (pinfunction "PCM_IN_7") (pintype "bidirectional"))
    )
    (net (code "88") (name "unconnected-(U13-PCM_OUT-Pad6)") (class "Default")
      (node (ref "U13") (pin "6") (pinfunction "PCM_OUT_6") (pintype "bidirectional"))
    )
    (net (code "89") (name "unconnected-(U13-PCN_SYNC-Pad8)") (class "Default")
      (node (ref "U13") (pin "8") (pinfunction "PCN_SYNC_8") (pintype "bidirectional"))
    )
    (net (code "90") (name "unconnected-(U13-PIO0-Pad23)") (class "Default")
      (node (ref "U13") (pin "23") (pinfunction "PIO0_23") (pintype "bidirectional"))
    )
    (net (code "91") (name "unconnected-(U13-PIO1-Pad24)") (class "Default")
      (node (ref "U13") (pin "24") (pinfunction "PIO1_24") (pintype "bidirectional"))
    )
    (net (code "92") (name "unconnected-(U13-PIO2-Pad25)") (class "Default")
      (node (ref "U13") (pin "25") (pinfunction "PIO2_25") (pintype "bidirectional"))
    )
    (net (code "93") (name "unconnected-(U13-PIO3-Pad26)") (class "Default")
      (node (ref "U13") (pin "26") (pinfunction "PIO3_26") (pintype "bidirectional"))
    )
    (net (code "94") (name "unconnected-(U13-PIO4-Pad27)") (class "Default")
      (node (ref "U13") (pin "27") (pinfunction "PIO4_27") (pintype "bidirectional"))
    )
    (net (code "95") (name "unconnected-(U13-PIO5-Pad28)") (class "Default")
      (node (ref "U13") (pin "28") (pinfunction "PIO5_28") (pintype "bidirectional"))
    )
    (net (code "96") (name "unconnected-(U13-PIO6-Pad29)") (class "Default")
      (node (ref "U13") (pin "29") (pinfunction "PIO6_29") (pintype "bidirectional"))
    )
    (net (code "97") (name "unconnected-(U13-PIO7-Pad30)") (class "Default")
      (node (ref "U13") (pin "30") (pinfunction "PIO7_30") (pintype "bidirectional"))
    )
    (net (code "98") (name "unconnected-(U13-PIO8-Pad31)") (class "Default")
      (node (ref "U13") (pin "31") (pinfunction "PIO8_31") (pintype "bidirectional"))
    )
    (net (code "99") (name "unconnected-(U13-PIO9-Pad32)") (class "Default")
      (node (ref "U13") (pin "32") (pinfunction "PIO9_32") (pintype "bidirectional"))
    )
    (net (code "100") (name "unconnected-(U13-PIO10-Pad33)") (class "Default")
      (node (ref "U13") (pin "33") (pinfunction "PIO10_33") (pintype "bidirectional"))
    )
    (net (code "101") (name "unconnected-(U13-PIO11-Pad34)") (class "Default")
      (node (ref "U13") (pin "34") (pinfunction "PIO11_34") (pintype "bidirectional"))
    )
    (net (code "102") (name "unconnected-(U13-RST-Pad11)") (class "Default")
      (node (ref "U13") (pin "11") (pinfunction "RST_11") (pintype "bidirectional"))
    )
    (net (code "103") (name "unconnected-(U13-RTS-Pad4)") (class "Default")
      (node (ref "U13") (pin "4") (pinfunction "RTS_4") (pintype "bidirectional"))
    )
    (net (code "104") (name "unconnected-(U13-VBUSD+-Pad20)") (class "Default")
      (node (ref "U13") (pin "20") (pinfunction "VBUSD+_20") (pintype "bidirectional"))
    )
    (net (code "105") (name "unconnected-(U13-VBUSD--Pad15)") (class "Default")
      (node (ref "U13") (pin "15") (pinfunction "VBUSD-_15") (pintype "bidirectional"))
    )
    (net (code "106") (name "unconnected-(U15-NC-Pad4)") (class "Default")
      (node (ref "U15") (pin "4") (pinfunction "NC_4") (pintype "bidirectional"))
    )
    (net (code "107") (name "unconnected-(U15-NC2-Pad5)") (class "Default")
      (node (ref "U15") (pin "5") (pinfunction "NC2_5") (pintype "bidirectional"))
    )
    (net (code "108") (name "unconnected-(U15-NC3-Pad6)") (class "Default")
      (node (ref "U15") (pin "6") (pinfunction "NC3_6") (pintype "bidirectional"))
    )
    (net (code "109") (name "unconnected-(U15-NC4-Pad7)") (class "Default")
      (node (ref "U15") (pin "7") (pinfunction "NC4_7") (pintype "bidirectional"))
    )
  )
)
